# Ifargan_door_lock_with_PIR.net
KiCad netlist of a schematic drawn in EAGLE
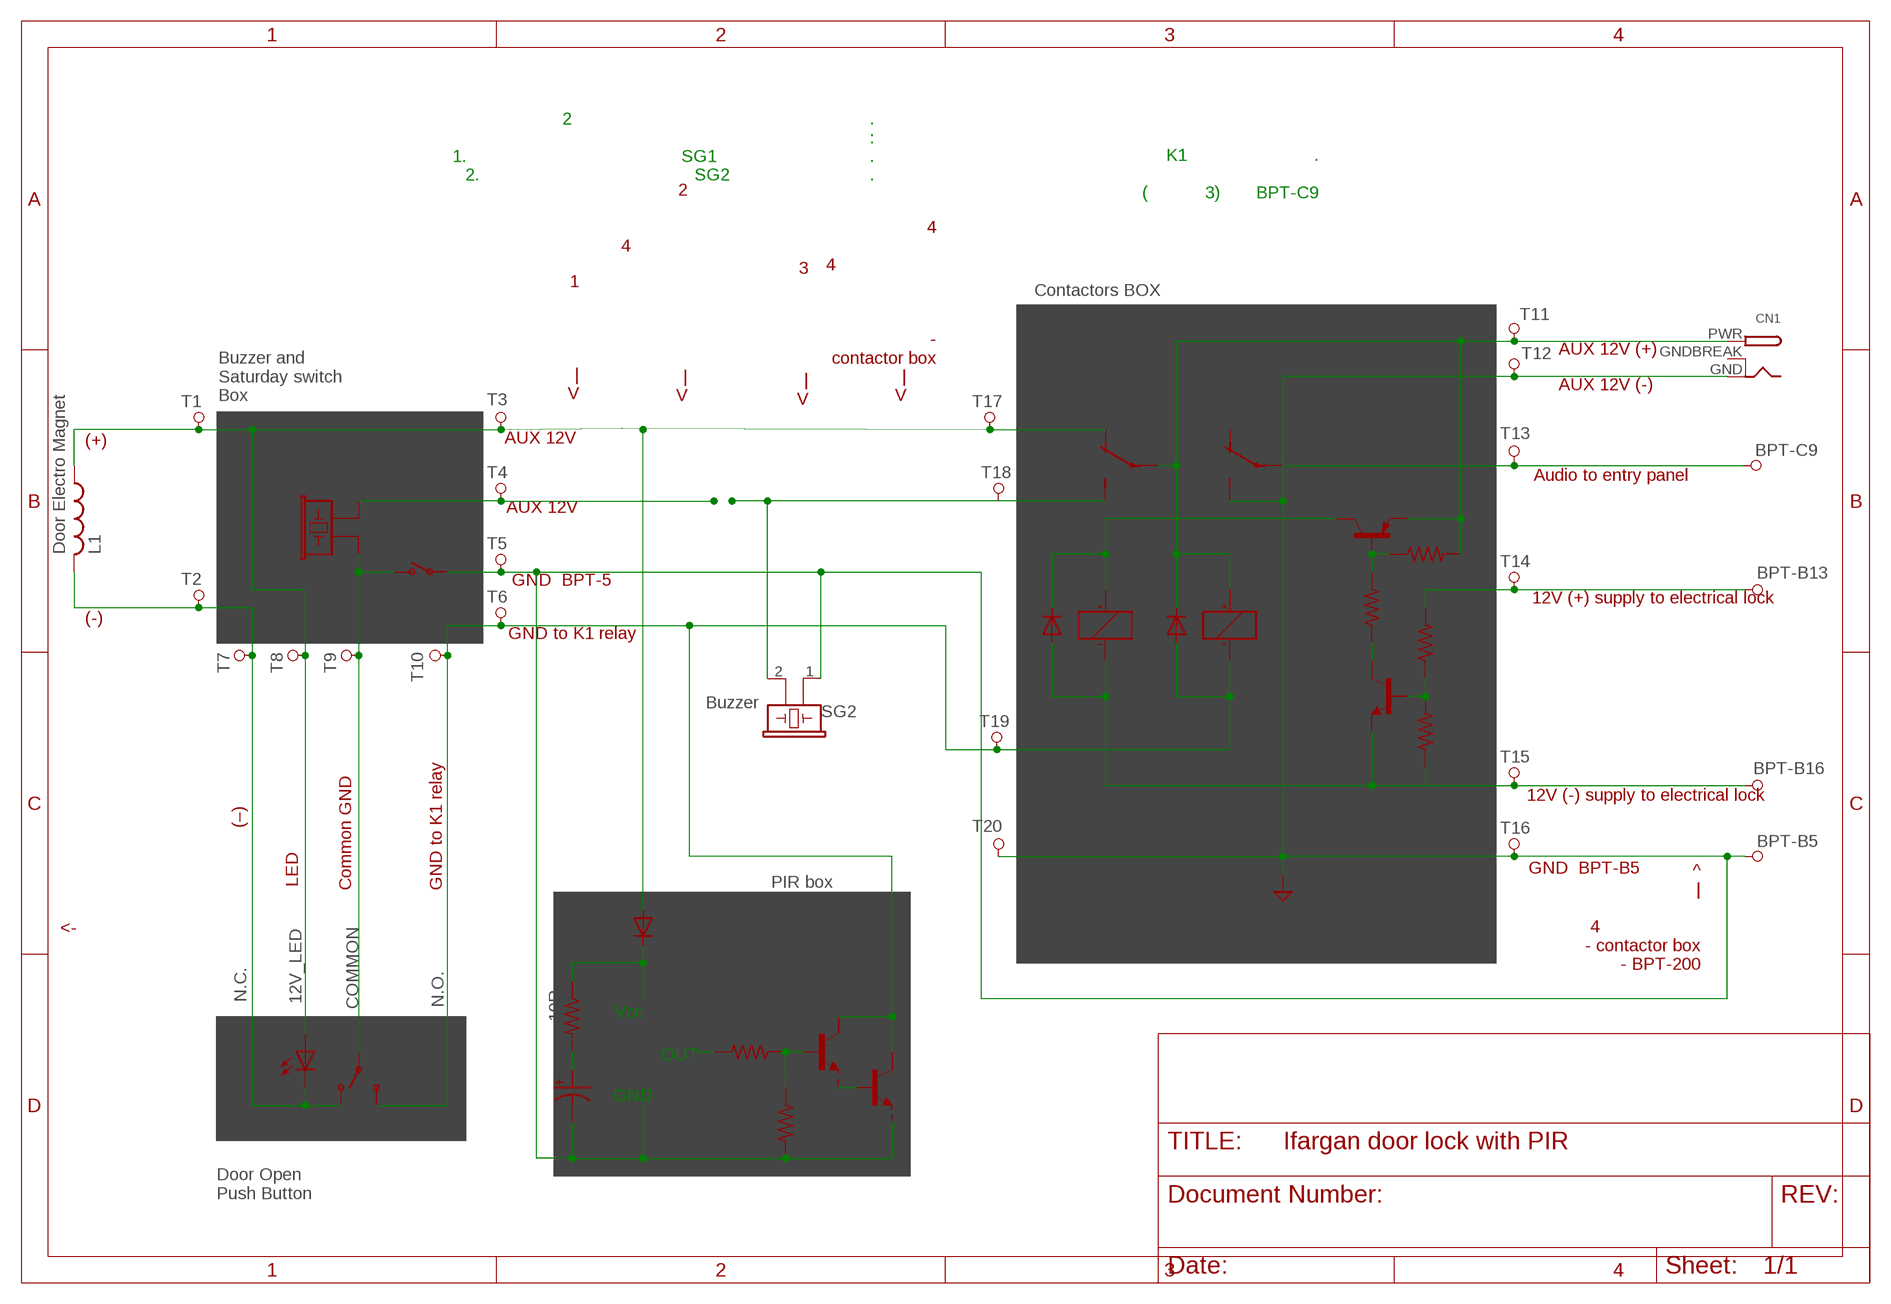
[diagram p0: schematic, sheet 1]

(export (version "E")
  (design (tool "Eeschema 10.0.6"))
  (components
    (comp (ref "BPT-B5")
      (value "PAD_TERMINAL-4.1MMROUND")
      (footprint "eagle-import:PAD_ROUND_4.1MM")
      (libsource (lib "eagle-import") (part "PAD_TERMINAL-4.1MMROUND"))
    )
    (comp (ref "BPT-B13")
      (value "PAD_TERMINAL-4.1MMROUND")
      (footprint "eagle-import:PAD_ROUND_4.1MM")
      (libsource (lib "eagle-import") (part "PAD_TERMINAL-4.1MMROUND"))
    )
    (comp (ref "BPT-B16")
      (value "PAD_TERMINAL-4.1MMROUND")
      (footprint "eagle-import:PAD_ROUND_4.1MM")
      (libsource (lib "eagle-import") (part "PAD_TERMINAL-4.1MMROUND"))
    )
    (comp (ref "BPT-C9")
      (value "PAD_TERMINAL-4.1MMROUND")
      (footprint "eagle-import:PAD_ROUND_4.1MM")
      (libsource (lib "eagle-import") (part "PAD_TERMINAL-4.1MMROUND"))
    )
    (comp (ref "C1")
      (value "470UF")
      (footprint "eagle-import:EIA3216")
      (libsource (lib "eagle-import") (part "CAP_POL1206"))
    )
    (comp (ref "CN1")
      (value "DCBARRELPTH")
      (footprint "eagle-import:DCJACK_2MM_PTH")
      (libsource (lib "eagle-import") (part "DCBARRELPTH"))
    )
    (comp (ref "D1")
      (value "1N4004")
      (footprint "eagle-import:DO41-10")
      (libsource (lib "eagle-import") (part "diode_1N4004"))
    )
    (comp (ref "D2")
      (value "1N4004")
      (footprint "eagle-import:DO41-10")
      (libsource (lib "eagle-import") (part "diode_1N4004"))
    )
    (comp (ref "D3")
      (value "1N4004")
      (footprint "eagle-import:DO41-10")
      (libsource (lib "eagle-import") (part "1N4004"))
    )
    (comp (ref "K1")
      (value "Relay")
      (footprint "eagle-import:DS2Y")
      (fields (field (name "MPN") "DS2Y-S-DC1.5V"))
      (libsource (lib "eagle-import") (part "DS2Y-S-DC1.5V"))
    )
    (comp (ref "K2")
      (value "Relay")
      (footprint "eagle-import:DS2Y")
      (fields (field (name "MPN") "DS2Y-S-DC1.5V"))
      (libsource (lib "eagle-import") (part "DS2Y-S-DC1.5V"))
    )
    (comp (ref "L1")
      (value "Door Electro Magnet")
      (footprint "eagle-import:IRF-3")
      (libsource (lib "eagle-import") (part "L-USIRF-3"))
    )
    (comp (ref "LED1")
      (value "LED")
      (footprint "eagle-import:SMARTLED-TTW")
      (libsource (lib "eagle-import") (part "LED"))
    )
    (comp (ref "Q1")
      (value "2N2905")
      (footprint "eagle-import:TO5")
      (libsource (lib "eagle-import") (part "2N2905"))
    )
    (comp (ref "Q2")
      (value "2N2219")
      (footprint "eagle-import:TO5")
      (libsource (lib "eagle-import") (part "2N2219"))
    )
    (comp (ref "R1")
      (value "10K")
      (footprint "eagle-import:0207_15")
      (libsource (lib "eagle-import") (part "R-US_0207/15"))
    )
    (comp (ref "R2")
      (value "1K")
      (footprint "eagle-import:0207_15")
      (libsource (lib "eagle-import") (part "R-US_0207/15"))
    )
    (comp (ref "R3")
      (value "1K")
      (footprint "eagle-import:0207_15")
      (libsource (lib "eagle-import") (part "R-US_0207/15"))
    )
    (comp (ref "R4")
      (value "10K")
      (footprint "eagle-import:0207_15")
      (libsource (lib "eagle-import") (part "R-US_0207/15"))
    )
    (comp (ref "R5")
      (value "100K")
      (footprint "eagle-import:0207_15")
      (libsource (lib "eagle-import") (part "resistor_R-US_0207/15"))
    )
    (comp (ref "R6")
      (value "100K")
      (footprint "eagle-import:0207_15")
      (libsource (lib "eagle-import") (part "resistor_R-US_0207/15"))
    )
    (comp (ref "R7")
      (value "10R")
      (footprint "eagle-import:0207_15")
      (libsource (lib "eagle-import") (part "resistor_R-US_0207/15"))
    )
    (comp (ref "S1")
      (value "Door Open P.B.")
      (footprint "eagle-import:KPS-1290")
      (libsource (lib "eagle-import") (part "SWITCH_SPDT"))
    )
    (comp (ref "S2")
      (value "Saturday SW")
      (footprint "eagle-import:SPST_SMT_19192")
      (libsource (lib "eagle-import") (part "SWITCH_SPST"))
    )
    (comp (ref "SG1")
      (value "Buzzer")
      (footprint "eagle-import:F_EE21P")
      (libsource (lib "eagle-import") (part "F/EE21P"))
    )
    (comp (ref "SG2")
      (value "Buzzer")
      (footprint "eagle-import:F_EE21P")
      (libsource (lib "eagle-import") (part "F/EE21P"))
    )
    (comp (ref "T1")
      (value "PAD_TERMINAL-4.1MMROUND")
      (footprint "eagle-import:PAD_ROUND_4.1MM")
      (libsource (lib "eagle-import") (part "PAD_TERMINAL-4.1MMROUND"))
    )
    (comp (ref "T2")
      (value "PAD_TERMINAL-4.1MMROUND")
      (footprint "eagle-import:PAD_ROUND_4.1MM")
      (libsource (lib "eagle-import") (part "PAD_TERMINAL-4.1MMROUND"))
    )
    (comp (ref "T3")
      (value "PAD_TERMINAL-4.1MMROUND")
      (footprint "eagle-import:PAD_ROUND_4.1MM")
      (libsource (lib "eagle-import") (part "PAD_TERMINAL-4.1MMROUND"))
    )
    (comp (ref "T4")
      (value "PAD_TERMINAL-4.1MMROUND")
      (footprint "eagle-import:PAD_ROUND_4.1MM")
      (libsource (lib "eagle-import") (part "PAD_TERMINAL-4.1MMROUND"))
    )
    (comp (ref "T5")
      (value "PAD_TERMINAL-4.1MMROUND")
      (footprint "eagle-import:PAD_ROUND_4.1MM")
      (libsource (lib "eagle-import") (part "PAD_TERMINAL-4.1MMROUND"))
    )
    (comp (ref "T6")
      (value "PAD_TERMINAL-4.1MMROUND")
      (footprint "eagle-import:PAD_ROUND_4.1MM")
      (libsource (lib "eagle-import") (part "PAD_TERMINAL-4.1MMROUND"))
    )
    (comp (ref "T7")
      (value "PAD_TERMINAL-4.1MMROUND")
      (footprint "eagle-import:PAD_ROUND_4.1MM")
      (libsource (lib "eagle-import") (part "PAD_TERMINAL-4.1MMROUND"))
    )
    (comp (ref "T8")
      (value "PAD_TERMINAL-4.1MMROUND")
      (footprint "eagle-import:PAD_ROUND_4.1MM")
      (libsource (lib "eagle-import") (part "PAD_TERMINAL-4.1MMROUND"))
    )
    (comp (ref "T9")
      (value "PAD_TERMINAL-4.1MMROUND")
      (footprint "eagle-import:PAD_ROUND_4.1MM")
      (libsource (lib "eagle-import") (part "PAD_TERMINAL-4.1MMROUND"))
    )
    (comp (ref "T10")
      (value "PAD_TERMINAL-4.1MMROUND")
      (footprint "eagle-import:PAD_ROUND_4.1MM")
      (libsource (lib "eagle-import") (part "PAD_TERMINAL-4.1MMROUND"))
    )
    (comp (ref "T11")
      (value "PAD_TERMINAL-4.1MMROUND")
      (footprint "eagle-import:PAD_ROUND_4.1MM")
      (libsource (lib "eagle-import") (part "PAD_TERMINAL-4.1MMROUND"))
    )
    (comp (ref "T12")
      (value "PAD_TERMINAL-4.1MMROUND")
      (footprint "eagle-import:PAD_ROUND_4.1MM")
      (libsource (lib "eagle-import") (part "PAD_TERMINAL-4.1MMROUND"))
    )
    (comp (ref "T13")
      (value "PAD_TERMINAL-4.1MMROUND")
      (footprint "eagle-import:PAD_ROUND_4.1MM")
      (libsource (lib "eagle-import") (part "PAD_TERMINAL-4.1MMROUND"))
    )
    (comp (ref "T14")
      (value "PAD_TERMINAL-4.1MMROUND")
      (footprint "eagle-import:PAD_ROUND_4.1MM")
      (libsource (lib "eagle-import") (part "PAD_TERMINAL-4.1MMROUND"))
    )
    (comp (ref "T15")
      (value "PAD_TERMINAL-4.1MMROUND")
      (footprint "eagle-import:PAD_ROUND_4.1MM")
      (libsource (lib "eagle-import") (part "PAD_TERMINAL-4.1MMROUND"))
    )
    (comp (ref "T16")
      (value "PAD_TERMINAL-4.1MMROUND")
      (footprint "eagle-import:PAD_ROUND_4.1MM")
      (libsource (lib "eagle-import") (part "PAD_TERMINAL-4.1MMROUND"))
    )
    (comp (ref "T17")
      (value "PAD_TERMINAL-4.1MMROUND")
      (footprint "eagle-import:PAD_ROUND_4.1MM")
      (libsource (lib "eagle-import") (part "PAD_TERMINAL-4.1MMROUND"))
    )
    (comp (ref "T18")
      (value "PAD_TERMINAL-4.1MMROUND")
      (footprint "eagle-import:PAD_ROUND_4.1MM")
      (libsource (lib "eagle-import") (part "PAD_TERMINAL-4.1MMROUND"))
    )
    (comp (ref "T19")
      (value "PAD_TERMINAL-4.1MMROUND")
      (footprint "eagle-import:PAD_ROUND_4.1MM")
      (libsource (lib "eagle-import") (part "PAD_TERMINAL-4.1MMROUND"))
    )
    (comp (ref "T20")
      (value "PAD_TERMINAL-4.1MMROUND")
      (footprint "eagle-import:PAD_ROUND_4.1MM")
      (libsource (lib "eagle-import") (part "PAD_TERMINAL-4.1MMROUND"))
    )
    (comp (ref "T21")
      (value "2N2222")
      (footprint "eagle-import:TO92-EBC-OVAL")
      (libsource (lib "eagle-import") (part "2N2222"))
    )
    (comp (ref "T22")
      (value "2N2222")
      (footprint "eagle-import:TO92-EBC-OVAL")
      (libsource (lib "eagle-import") (part "2N2222"))
    )
  )
  (nets
    (net (code "1") (name "/12V_LED") (class "Default")
      (node (ref "K2") (pin "6") (pinfunction "O_6") (pintype "passive"))
      (node (ref "L1") (pin "1") (pinfunction "1_1") (pintype "passive"))
      (node (ref "LED1") (pin "A@1") (pinfunction "A_A@1") (pintype "passive"))
      (node (ref "T1") (pin "P") (pinfunction "P_P") (pintype "passive"))
      (node (ref "T17") (pin "P") (pinfunction "P_P") (pintype "passive"))
      (node (ref "T3") (pin "P") (pinfunction "P_P") (pintype "passive"))
      (node (ref "T8") (pin "P") (pinfunction "P_P") (pintype "passive"))
    )
    (net (code "2") (name "/AUX-12V") (class "Default")
      (node (ref "CN1") (pin "PWR") (pinfunction "PWR_PWR") (pintype "power_in"))
      (node (ref "D2") (pin "C") (pinfunction "C_C") (pintype "passive"))
      (node (ref "K1") (pin "1") (pinfunction "+_1") (pintype "passive"))
      (node (ref "K2") (pin "4") (pinfunction "P_4") (pintype "passive"))
      (node (ref "Q1") (pin "1") (pinfunction "E_1") (pintype "passive"))
      (node (ref "R1") (pin "2") (pinfunction "2_2") (pintype "passive"))
      (node (ref "T11") (pin "P") (pinfunction "P_P") (pintype "passive"))
    )
    (net (code "3") (name "/COMMON") (class "Default")
      (node (ref "S1") (pin "P") (pinfunction "P_P") (pintype "passive"))
      (node (ref "S2") (pin "C") (pinfunction "S_C") (pintype "passive"))
      (node (ref "SG1") (pin "1") (pinfunction "1_1") (pintype "passive"))
      (node (ref "T9") (pin "P") (pinfunction "P_P") (pintype "passive"))
    )
    (net (code "4") (name "/GNDBREAK") (class "Default")
      (node (ref "CN1") (pin "GNDBREAK") (pinfunction "GNDBREAK_GNDBREAK") (pintype "power_in"))
    )
    (net (code "5") (name "/N.C.") (class "Default")
      (node (ref "L1") (pin "2") (pinfunction "2_2") (pintype "passive"))
      (node (ref "LED1") (pin "C@1") (pinfunction "C_C@1") (pintype "passive"))
      (node (ref "S1") (pin "O") (pinfunction "O_O") (pintype "passive"))
      (node (ref "T2") (pin "P") (pinfunction "P_P") (pintype "passive"))
      (node (ref "T7") (pin "P") (pinfunction "P_P") (pintype "passive"))
    )
    (net (code "6") (name "/N.O.") (class "Default")
      (node (ref "D2") (pin "A") (pinfunction "A_A") (pintype "passive"))
      (node (ref "K1") (pin "16") (pinfunction "-_16") (pintype "passive"))
      (node (ref "S1") (pin "S") (pinfunction "S_S") (pintype "passive"))
      (node (ref "T10") (pin "P") (pinfunction "P_P") (pintype "passive"))
      (node (ref "T19") (pin "P") (pinfunction "P_P") (pintype "passive"))
      (node (ref "T21") (pin "C") (pinfunction "C_C") (pintype "passive"))
      (node (ref "T22") (pin "C") (pinfunction "C_C") (pintype "passive"))
      (node (ref "T6") (pin "P") (pinfunction "P_P") (pintype "passive"))
    )
    (net (code "7") (name "GND") (class "Default")
      (node (ref "BPT-B5") (pin "P") (pinfunction "P_P") (pintype "passive"))
      (node (ref "C1") (pin "C") (pinfunction "-_C") (pintype "passive"))
      (node (ref "CN1") (pin "GND") (pinfunction "GND_GND") (pintype "power_in"))
      (node (ref "K1") (pin "8") (pinfunction "S_8") (pintype "passive"))
      (node (ref "R5") (pin "2") (pinfunction "2_2") (pintype "passive"))
      (node (ref "S2") (pin "B") (pinfunction "P_B") (pintype "passive"))
      (node (ref "SG2") (pin "1") (pinfunction "1_1") (pintype "passive"))
      (node (ref "T12") (pin "P") (pinfunction "P_P") (pintype "passive"))
      (node (ref "T16") (pin "P") (pinfunction "P_P") (pintype "passive"))
      (node (ref "T20") (pin "P") (pinfunction "P_P") (pintype "passive"))
      (node (ref "T22") (pin "E") (pinfunction "E_E") (pintype "passive"))
      (node (ref "T5") (pin "P") (pinfunction "P_P") (pintype "passive"))
    )
    (net (code "8") (name "Net-(BPT-B13-PadP)") (class "Default")
      (node (ref "BPT-B13") (pin "P") (pinfunction "P_P") (pintype "passive"))
      (node (ref "R3") (pin "2") (pinfunction "2_2") (pintype "passive"))
      (node (ref "T14") (pin "P") (pinfunction "P_P") (pintype "passive"))
    )
    (net (code "9") (name "Net-(C1-+)") (class "Default")
      (node (ref "C1") (pin "A") (pinfunction "+_A") (pintype "passive"))
      (node (ref "R7") (pin "2") (pinfunction "2_2") (pintype "passive"))
    )
    (net (code "10") (name "Net-(D3-PadC)") (class "Default")
      (node (ref "D3") (pin "C") (pinfunction "C_C") (pintype "passive"))
      (node (ref "R7") (pin "1") (pinfunction "1_1") (pintype "passive"))
    )
    (net (code "11") (name "Net-(K1B-P)") (class "Default")
      (node (ref "BPT-C9") (pin "P") (pinfunction "P_P") (pintype "passive"))
      (node (ref "K1") (pin "4") (pinfunction "P_4") (pintype "passive"))
    )
    (net (code "12") (name "Net-(K2A-+)") (class "Default")
      (node (ref "D1") (pin "C") (pinfunction "C_C") (pintype "passive"))
      (node (ref "K2") (pin "1") (pinfunction "+_1") (pintype "passive"))
      (node (ref "Q1") (pin "3") (pinfunction "C_3") (pintype "passive"))
    )
    (net (code "13") (name "Net-(K2A--)") (class "Default")
      (node (ref "BPT-B16") (pin "P") (pinfunction "P_P") (pintype "passive"))
      (node (ref "D1") (pin "A") (pinfunction "A_A") (pintype "passive"))
      (node (ref "K2") (pin "16") (pinfunction "-_16") (pintype "passive"))
      (node (ref "Q2") (pin "1") (pinfunction "E_1") (pintype "passive"))
      (node (ref "R4") (pin "1") (pinfunction "1_1") (pintype "passive"))
      (node (ref "T15") (pin "P") (pinfunction "P_P") (pintype "passive"))
    )
    (net (code "14") (name "Net-(K2B-S)") (class "Default")
      (node (ref "K2") (pin "8") (pinfunction "S_8") (pintype "passive"))
      (node (ref "SG2") (pin "2") (pinfunction "2_2") (pintype "passive"))
      (node (ref "T18") (pin "P") (pinfunction "P_P") (pintype "passive"))
    )
    (net (code "15") (name "Net-(Q1-B)") (class "Default")
      (node (ref "Q1") (pin "2") (pinfunction "B_2") (pintype "passive"))
      (node (ref "R1") (pin "1") (pinfunction "1_1") (pintype "passive"))
      (node (ref "R2") (pin "2") (pinfunction "2_2") (pintype "passive"))
    )
    (net (code "16") (name "Net-(Q2-B)") (class "Default")
      (node (ref "Q2") (pin "2") (pinfunction "B_2") (pintype "passive"))
      (node (ref "R3") (pin "1") (pinfunction "1_1") (pintype "passive"))
      (node (ref "R4") (pin "2") (pinfunction "2_2") (pintype "passive"))
    )
    (net (code "17") (name "Net-(Q2-C)") (class "Default")
      (node (ref "Q2") (pin "3") (pinfunction "C_3") (pintype "passive"))
      (node (ref "R2") (pin "1") (pinfunction "1_1") (pintype "passive"))
    )
    (net (code "18") (name "Net-(R5-Pad1)") (class "Default")
      (node (ref "R5") (pin "1") (pinfunction "1_1") (pintype "passive"))
      (node (ref "R6") (pin "1") (pinfunction "1_1") (pintype "passive"))
      (node (ref "T21") (pin "B") (pinfunction "B_B") (pintype "passive"))
    )
    (net (code "19") (name "Net-(SG1-Pad2)") (class "Default")
      (node (ref "SG1") (pin "2") (pinfunction "2_2") (pintype "passive"))
      (node (ref "T4") (pin "P") (pinfunction "P_P") (pintype "passive"))
    )
    (net (code "20") (name "Net-(T21-PadE)") (class "Default")
      (node (ref "T21") (pin "E") (pinfunction "E_E") (pintype "passive"))
      (node (ref "T22") (pin "B") (pinfunction "B_B") (pintype "passive"))
    )
    (net (code "21") (name "unconnected-(D3-PadA)") (class "Default")
      (node (ref "D3") (pin "A") (pinfunction "A_A") (pintype "passive"))
    )
    (net (code "22") (name "unconnected-(K1B-O-Pad6)") (class "Default")
      (node (ref "K1") (pin "6") (pinfunction "O_6") (pintype "passive"))
    )
    (net (code "23") (name "unconnected-(R6-Pad2)") (class "Default")
      (node (ref "R6") (pin "2") (pinfunction "2_2") (pintype "passive"))
    )
    (net (code "24") (name "unconnected-(T13-PadP)") (class "Default")
      (node (ref "T13") (pin "P") (pinfunction "P_P") (pintype "passive"))
    )
  )
)
